# top.net
KiCad netlist of a schematic drawn in Altium Designer
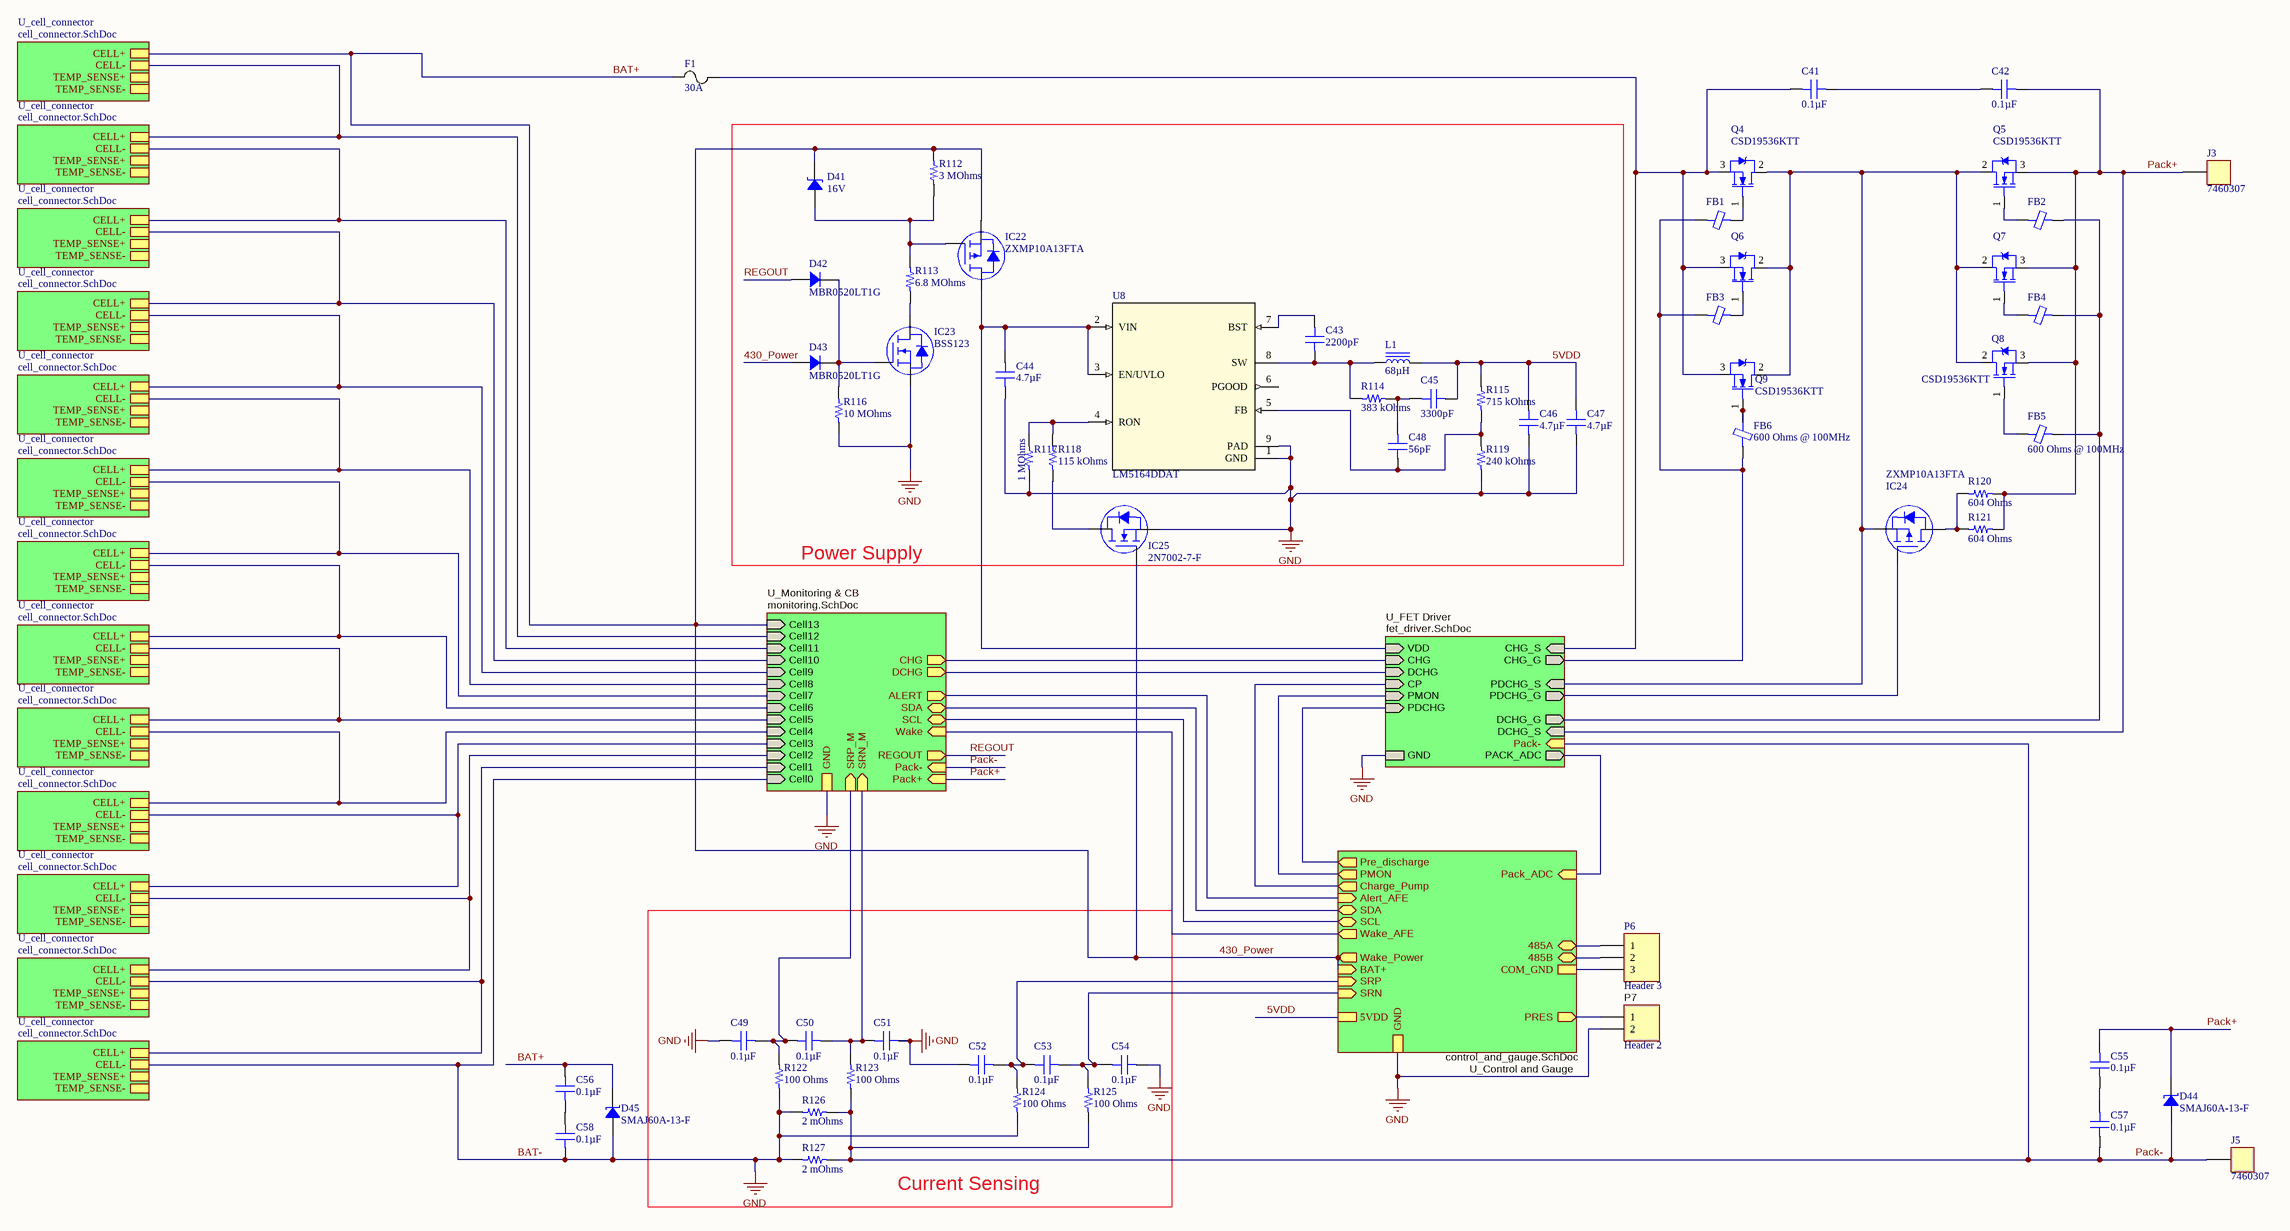
[diagram p0: top.SchDoc]

(export (version "E")
  (design (tool "Eeschema 10.0.6"))
  (components
    (comp (ref "C41")
      (value "0.1µF")
      (footprint "CAP 0603_1608")
      (description "CAP CER 0.1UF 100V X7R 0603")
      (fields
        (field (name "PART NUMBER") "GCJ188R72A104KA01D")
        (field (name "MANUFACTURER") "Murata Electronics")
      )
      (libsource (lib "Celestial Altium Library - altium_library") (part "Capacitor"))
    )
    (comp (ref "C42")
      (value "0.1µF")
      (footprint "CAP 0603_1608")
      (description "CAP CER 0.1UF 100V X7R 0603")
      (fields
        (field (name "PART NUMBER") "GCJ188R72A104KA01D")
        (field (name "MANUFACTURER") "Murata Electronics")
      )
      (libsource (lib "Celestial Altium Library - altium_library") (part "Capacitor"))
    )
    (comp (ref "C43")
      (value "2200pF")
      (footprint "CAP 0603_1608")
      (description "CAP CER 2200PF 50V C0G 0603")
      (fields
        (field (name "PART NUMBER") "C1608C0G1H222J080AA")
        (field (name "MANUFACTURER") "TDK Corporation")
      )
      (libsource (lib "Celestial Altium Library - altium_library") (part "Capacitor"))
    )
    (comp (ref "C44")
      (value "4.7µF")
      (footprint "CAP 1210_3225 - 2.2MM")
      (description "CAP CER 4.7UF 100V X7S 1210")
      (fields
        (field (name "PART NUMBER") "C3225X7S2A475K200AB")
        (field (name "MANUFACTURER") "TDK Corporation")
      )
      (libsource (lib "Celestial Altium Library - altium_library") (part "Capacitor"))
    )
    (comp (ref "C45")
      (value "3300pF")
      (footprint "CAP 0603_1608")
      (description "CAP CER 3300PF 50V X7R 0603")
      (fields
        (field (name "PART NUMBER") "CGA3E2X7R1H332K080AA")
        (field (name "MANUFACTURER") "TDK Corporation")
      )
      (libsource (lib "Celestial Altium Library - altium_library") (part "Capacitor"))
    )
    (comp (ref "C46")
      (value "4.7µF")
      (footprint "CAP 0805_2012")
      (description "CAP CER 4.7UF 16V X7R 0805")
      (fields (field (name "PART NUMBER") "CC0805KKX7R7BB475") (field (name "MANUFACTURER") "Yageo"))
      (libsource (lib "Celestial Altium Library - altium_library") (part "Capacitor"))
    )
    (comp (ref "C47")
      (value "4.7µF")
      (footprint "CAP 0805_2012")
      (description "CAP CER 4.7UF 16V X7R 0805")
      (fields (field (name "PART NUMBER") "CC0805KKX7R7BB475") (field (name "MANUFACTURER") "Yageo"))
      (libsource (lib "Celestial Altium Library - altium_library") (part "Capacitor"))
    )
    (comp (ref "C48")
      (value "56pF")
      (footprint "CAP 0603_1608")
      (description "CAP CER 56PF 50V C0G 0603")
      (fields
        (field (name "PART NUMBER") "CGA3E2C0G1H560J080AA")
        (field (name "MANUFACTURER") "TDK Corporation")
      )
      (libsource (lib "Celestial Altium Library - altium_library") (part "Capacitor"))
    )
    (comp (ref "C49")
      (value "0.1µF")
      (footprint "CAP 0603_1608")
      (description "CAP CER 0.1UF 50V X7R 0603")
      (fields
        (field (name "PART NUMBER") "GCJ188R71H104KA12D")
        (field (name "MANUFACTURER") "Murata Electronics")
      )
      (libsource (lib "Celestial Altium Library - altium_library") (part "Capacitor"))
    )
    (comp (ref "C50")
      (value "0.1µF")
      (footprint "CAP 0603_1608")
      (description "CAP CER 0.1UF 50V X7R 0603")
      (fields
        (field (name "PART NUMBER") "GCJ188R71H104KA12D")
        (field (name "MANUFACTURER") "Murata Electronics")
      )
      (libsource (lib "Celestial Altium Library - altium_library") (part "Capacitor"))
    )
    (comp (ref "C51")
      (value "0.1µF")
      (footprint "CAP 0603_1608")
      (description "CAP CER 0.1UF 50V X7R 0603")
      (fields
        (field (name "PART NUMBER") "GCJ188R71H104KA12D")
        (field (name "MANUFACTURER") "Murata Electronics")
      )
      (libsource (lib "Celestial Altium Library - altium_library") (part "Capacitor"))
    )
    (comp (ref "C52")
      (value "0.1µF")
      (footprint "CAP 0603_1608")
      (description "CAP CER 0.1UF 50V X7R 0603")
      (fields
        (field (name "PART NUMBER") "GCJ188R71H104KA12D")
        (field (name "MANUFACTURER") "Murata Electronics")
      )
      (libsource (lib "Celestial Altium Library - altium_library") (part "Capacitor"))
    )
    (comp (ref "C53")
      (value "0.1µF")
      (footprint "CAP 0603_1608")
      (description "CAP CER 0.1UF 50V X7R 0603")
      (fields
        (field (name "PART NUMBER") "GCJ188R71H104KA12D")
        (field (name "MANUFACTURER") "Murata Electronics")
      )
      (libsource (lib "Celestial Altium Library - altium_library") (part "Capacitor"))
    )
    (comp (ref "C54")
      (value "0.1µF")
      (footprint "CAP 0603_1608")
      (description "CAP CER 0.1UF 50V X7R 0603")
      (fields
        (field (name "PART NUMBER") "GCJ188R71H104KA12D")
        (field (name "MANUFACTURER") "Murata Electronics")
      )
      (libsource (lib "Celestial Altium Library - altium_library") (part "Capacitor"))
    )
    (comp (ref "C55")
      (value "0.1µF")
      (footprint "CAP 0603_1608")
      (description "CAP CER 0.1UF 100V X7R 0603")
      (fields
        (field (name "PART NUMBER") "GCJ188R72A104KA01D")
        (field (name "MANUFACTURER") "Murata Electronics")
      )
      (libsource (lib "Celestial Altium Library - altium_library") (part "Capacitor"))
    )
    (comp (ref "C56")
      (value "0.1µF")
      (footprint "CAP 0603_1608")
      (description "CAP CER 0.1UF 100V X7R 0603")
      (fields
        (field (name "PART NUMBER") "GCJ188R72A104KA01D")
        (field (name "MANUFACTURER") "Murata Electronics")
      )
      (libsource (lib "Celestial Altium Library - altium_library") (part "Capacitor"))
    )
    (comp (ref "C57")
      (value "0.1µF")
      (footprint "CAP 0603_1608")
      (description "CAP CER 0.1UF 100V X7R 0603")
      (fields
        (field (name "PART NUMBER") "GCJ188R72A104KA01D")
        (field (name "MANUFACTURER") "Murata Electronics")
      )
      (libsource (lib "Celestial Altium Library - altium_library") (part "Capacitor"))
    )
    (comp (ref "C58")
      (value "0.1µF")
      (footprint "CAP 0603_1608")
      (description "CAP CER 0.1UF 100V X7R 0603")
      (fields
        (field (name "PART NUMBER") "GCJ188R72A104KA01D")
        (field (name "MANUFACTURER") "Murata Electronics")
      )
      (libsource (lib "Celestial Altium Library - altium_library") (part "Capacitor"))
    )
    (comp (ref "D41")
      (value "MMSZ5246B-7-F")
      (footprint "SOD-123")
      (description "DIODE ZENER 16V 500MW SOD123")
      (fields
        (field (name "MANUFACTURER") "Diodes Incorporated")
        (field (name "TOLERANCE") "±5%")
        (field (name "VOLTAGE - ZENER (NOM) (VZ)") "16V")
      )
      (libsource (lib "Celestial Altium Library - altium_library") (part "Diode Zener"))
    )
    (comp (ref "D42")
      (value "MBR0520LT1G")
      (footprint "SOD-123")
      (description "DIODE SCHOTTKY 20V 500MA SOD123")
      (fields (field (name "MANUFACTURER") "ON Semiconductor"))
      (libsource (lib "Celestial Altium Library - altium_library") (part "Diode"))
    )
    (comp (ref "D43")
      (value "MBR0520LT1G")
      (footprint "SOD-123")
      (description "DIODE SCHOTTKY 20V 500MA SOD123")
      (fields (field (name "MANUFACTURER") "ON Semiconductor"))
      (libsource (lib "Celestial Altium Library - altium_library") (part "Diode"))
    )
    (comp (ref "D44")
      (value "SMAJ60A-13-F")
      (footprint "DO214AC SMA")
      (description "TVS DIODE 60V 96.8V SMA")
      (fields (field (name "MANUFACTURER") "Diodes Incorporated"))
      (libsource (lib "Celestial Altium Library - altium_library") (part "DIODE TVS UNI"))
    )
    (comp (ref "D45")
      (value "SMAJ60A-13-F")
      (footprint "DO214AC SMA")
      (description "TVS DIODE 60V 96.8V SMA")
      (fields (field (name "MANUFACTURER") "Diodes Incorporated"))
      (libsource (lib "Celestial Altium Library - altium_library") (part "DIODE TVS UNI"))
    )
    (comp (ref "F1")
      (value "0456030.ER")
      (footprint "FUS_LITTELFUSE_0456_30A_LTF")
      (description "AC DC Fuse Board Mount (Cartridge Style Excluded) Surface Mount 2-SMD, Square End Block")
      (fields
        (field (name "MANUFACTURER") "Littelfuse")
        (field (name "FUSE CURRENT") "30A")
        (field (name "COPYRIGHT") "Copyright (C) 2018 Accelerated Designs. All rights reserved")
      )
      (libsource (lib "bms") (part "0456030.ER"))
    )
    (comp (ref "FB1")
      (value "600 Ohms @ 100MHz")
      (footprint "FER 0603_1608")
      (description "FERRITE BEAD 600 OHM 0603 1LN")
      (fields (field (name "PART NUMBER") "74279265") (field (name "MANUFACTURER") "Würth Elektronik"))
      (libsource (lib "Celestial Altium Library - altium_library") (part "Ferrite Chip"))
    )
    (comp (ref "FB2")
      (value "600 Ohms @ 100MHz")
      (footprint "FER 0603_1608")
      (description "FERRITE BEAD 600 OHM 0603 1LN")
      (fields (field (name "PART NUMBER") "74279265") (field (name "MANUFACTURER") "Würth Elektronik"))
      (libsource (lib "Celestial Altium Library - altium_library") (part "Ferrite Chip"))
    )
    (comp (ref "FB3")
      (value "600 Ohms @ 100MHz")
      (footprint "FER 0603_1608")
      (description "FERRITE BEAD 600 OHM 0603 1LN")
      (fields (field (name "PART NUMBER") "74279265") (field (name "MANUFACTURER") "Würth Elektronik"))
      (libsource (lib "Celestial Altium Library - altium_library") (part "Ferrite Chip"))
    )
    (comp (ref "FB4")
      (value "600 Ohms @ 100MHz")
      (footprint "FER 0603_1608")
      (description "FERRITE BEAD 600 OHM 0603 1LN")
      (fields (field (name "PART NUMBER") "74279265") (field (name "MANUFACTURER") "Würth Elektronik"))
      (libsource (lib "Celestial Altium Library - altium_library") (part "Ferrite Chip"))
    )
    (comp (ref "FB5")
      (value "600 Ohms @ 100MHz")
      (footprint "FER 0603_1608")
      (description "FERRITE BEAD 600 OHM 0603 1LN")
      (fields (field (name "PART NUMBER") "74279265") (field (name "MANUFACTURER") "Würth Elektronik"))
      (libsource (lib "Celestial Altium Library - altium_library") (part "Ferrite Chip"))
    )
    (comp (ref "FB6")
      (value "600 Ohms @ 100MHz")
      (footprint "FER 0603_1608")
      (description "FERRITE BEAD 600 OHM 0603 1LN")
      (fields (field (name "PART NUMBER") "74279265") (field (name "MANUFACTURER") "Würth Elektronik"))
      (libsource (lib "Celestial Altium Library - altium_library") (part "Ferrite Chip"))
    )
    (comp (ref "IC22")
      (value "ZXMP10A13FTA")
      (footprint "DIODES SOT-23-3")
      (description "MOSFET P-CH 100V 0.6A SOT23-3")
      (fields (field (name "MANUFACTURER") "Diodes Incorporated"))
      (libsource (lib "Celestial Altium Library - altium_library") (part "DIODES MOSFET P-CH SOT-23-3"))
    )
    (comp (ref "IC23")
      (value "BSS123")
      (footprint "ON SEMI SOT-23-3")
      (description "MOSFET N-CH 100V 170MA SOT-23")
      (fields (field (name "MANUFACTURER") "ON Semiconductor"))
      (libsource (lib "Celestial Altium Library - altium_library") (part "ON SEMI MOSFET N-CH SOT-23-3"))
    )
    (comp (ref "IC24")
      (value "ZXMP10A13FTA")
      (footprint "DIODES SOT-23-3")
      (description "MOSFET P-CH 100V 0.6A SOT23-3")
      (fields (field (name "MANUFACTURER") "Diodes Incorporated"))
      (libsource (lib "Celestial Altium Library - altium_library") (part "DIODES MOSFET P-CH SOT-23-3"))
    )
    (comp (ref "IC25")
      (value "2N7002-7-F")
      (footprint "DIODES SOT-23-3")
      (description "MOSFET N-CH 60V 115MA SOT23-3")
      (fields (field (name "MANUFACTURER") "Diodes Incorporated"))
      (libsource (lib "Celestial Altium Library - altium_library") (part "DIODES INC MOSFET N-CH SOT-23-3"))
    )
    (comp (ref "J3")
      (value "7460307")
      (footprint "7460307")
      (description "TERM REDCUBE M4 8PIN PCB 160A Current")
      (fields
        (field (name "MOUSER PART NUMBER") "710-7460307")
        (field (name "MANUFACTURER") "Wurth Electronics")
      )
      (libsource (lib "bms") (part "7460307"))
    )
    (comp (ref "J5")
      (value "7460307")
      (footprint "7460307")
      (description "TERM REDCUBE M4 8PIN PCB 160A Current")
      (fields
        (field (name "MOUSER PART NUMBER") "710-7460307")
        (field (name "MANUFACTURER") "Wurth Electronics")
      )
      (libsource (lib "bms") (part "7460307"))
    )
    (comp (ref "L1")
      (value "68µH")
      (footprint "TDK SLF10145")
      (description "FIXED IND 68UH 1.3A 168 MOHM SMD")
      (fields
        (field (name "PART NUMBER") "SLF10145T-680M1R2-PF")
        (field (name "MANUFACTURER") "TDK Corporation")
      )
      (libsource (lib "Celestial Altium Library - altium_library") (part "Inductor"))
    )
    (comp (ref "P6")
      (value "Header 3")
      (footprint "HDR1X3")
      (description "Header, 3-Pin")
      (fields (field (name "PUBLISHER") "Altium Limited"))
      (libsource (lib "Miscellaneous Connectors") (part "Header 3"))
    )
    (comp (ref "P7")
      (value "Header 2")
      (footprint "HDR1X2")
      (description "Header, 2-Pin")
      (fields (field (name "PUBLISHER") "Altium Limited"))
      (libsource (lib "Miscellaneous Connectors") (part "Header 2"))
    )
    (comp (ref "Q4")
      (value "CSD19536KTT")
      (footprint "DDPAK")
      (fields (field (name "MANUFACTURER") "Texas Instruments"))
      (libsource (lib "bms") (part "CSD19536KTT"))
    )
    (comp (ref "Q5")
      (value "CSD19536KTT")
      (footprint "DDPAK")
      (fields (field (name "MANUFACTURER") "Texas Instruments"))
      (libsource (lib "bms") (part "CSD19536KTT"))
    )
    (comp (ref "Q6")
      (value "CSD19536KTT")
      (footprint "DDPAK")
      (fields (field (name "MANUFACTURER") "Texas Instruments"))
      (libsource (lib "bms") (part "CSD19536KTT"))
    )
    (comp (ref "Q7")
      (value "CSD19536KTT")
      (footprint "DDPAK")
      (fields (field (name "MANUFACTURER") "Texas Instruments"))
      (libsource (lib "bms") (part "CSD19536KTT"))
    )
    (comp (ref "Q8")
      (value "CSD19536KTT")
      (footprint "DDPAK")
      (fields (field (name "MANUFACTURER") "Texas Instruments"))
      (libsource (lib "bms") (part "CSD19536KTT"))
    )
    (comp (ref "Q9")
      (value "CSD19536KTT")
      (footprint "DDPAK")
      (fields (field (name "MANUFACTURER") "Texas Instruments"))
      (libsource (lib "bms") (part "CSD19536KTT"))
    )
    (comp (ref "R112")
      (value "3 MOhms")
      (footprint "RES 0603_1608")
      (description "RES SMD 3M OHM 1% 1/10W 0603")
      (fields (field (name "PART NUMBER") "CRCW06033M00FKEA") (field (name "MANUFACTURER") "Vishay Dale"))
      (libsource (lib "Celestial Altium Library - altium_library") (part "Resistor"))
    )
    (comp (ref "R113")
      (value "6.8 MOhms")
      (footprint "RES 0603_1608")
      (description "RES SMD 6.8M OHM 1% 1/10W 0603")
      (fields (field (name "PART NUMBER") "CRCW06036M80FKEA") (field (name "MANUFACTURER") "Vishay Dale"))
      (libsource (lib "Celestial Altium Library - altium_library") (part "Resistor"))
    )
    (comp (ref "R114")
      (value "383 kOhms")
      (footprint "RES 0603_1608")
      (description "RES SMD 383K OHM 1% 1/10W 0603")
      (fields (field (name "PART NUMBER") "CRCW0603383KFKEA") (field (name "MANUFACTURER") "Vishay Dale"))
      (libsource (lib "Celestial Altium Library - altium_library") (part "Resistor"))
    )
    (comp (ref "R115")
      (value "715 kOhms")
      (footprint "RES 0603_1608")
      (description "RES SMD 715K OHM 1% 1/10W 0603")
      (fields (field (name "PART NUMBER") "CRCW0603715KFKEA") (field (name "MANUFACTURER") "Vishay Dale"))
      (libsource (lib "Celestial Altium Library - altium_library") (part "Resistor"))
    )
    (comp (ref "R116")
      (value "10 MOhms")
      (footprint "RES 0603_1608")
      (description "RES SMD 10M OHM 1% 1/10W 0603")
      (fields (field (name "PART NUMBER") "CRCW060310M0FKEA") (field (name "MANUFACTURER") "Vishay Dale"))
      (libsource (lib "Celestial Altium Library - altium_library") (part "Resistor"))
    )
    (comp (ref "R117")
      (value "1 MOhms")
      (footprint "RES 0603_1608")
      (description "RES SMD 1M OHM 1% 1/10W 0603")
      (fields (field (name "PART NUMBER") "CRCW06031M00FKEA") (field (name "MANUFACTURER") "Vishay Dale"))
      (libsource (lib "Celestial Altium Library - altium_library") (part "Resistor"))
    )
    (comp (ref "R118")
      (value "115 kOhms")
      (footprint "RES 0603_1608")
      (description "RES SMD 115K OHM 1% 1/10W 0603")
      (fields (field (name "PART NUMBER") "CRCW0603115KFKEA") (field (name "MANUFACTURER") "Vishay Dale"))
      (libsource (lib "Celestial Altium Library - altium_library") (part "Resistor"))
    )
    (comp (ref "R119")
      (value "240 kOhms")
      (footprint "RES 0603_1608")
      (description "RES SMD 240K OHM 1% 1/10W 0603")
      (fields (field (name "PART NUMBER") "CRCW0603240KFKEA") (field (name "MANUFACTURER") "Vishay Dale"))
      (libsource (lib "Celestial Altium Library - altium_library") (part "Resistor"))
    )
    (comp (ref "R120")
      (value "604 Ohms")
      (footprint "RES 2512_6432")
      (description "RES SMD 604 OHM 1% 1W 2512")
      (fields (field (name "PART NUMBER") "CRCW2512604RFKEG") (field (name "MANUFACTURER") "Vishay Dale"))
      (libsource (lib "Celestial Altium Library - altium_library") (part "Resistor"))
    )
    (comp (ref "R121")
      (value "604 Ohms")
      (footprint "RES 2512_6432")
      (description "RES SMD 604 OHM 1% 1W 2512")
      (fields (field (name "PART NUMBER") "CRCW2512604RFKEG") (field (name "MANUFACTURER") "Vishay Dale"))
      (libsource (lib "Celestial Altium Library - altium_library") (part "Resistor"))
    )
    (comp (ref "R122")
      (value "100 Ohms")
      (footprint "RES 0603_1608")
      (description "RES SMD 100 OHM 1% 1/10W 0603")
      (fields (field (name "PART NUMBER") "CRCW0603100RFKTA") (field (name "MANUFACTURER") "Vishay Dale"))
      (libsource (lib "Celestial Altium Library - altium_library") (part "Resistor"))
    )
    (comp (ref "R123")
      (value "100 Ohms")
      (footprint "RES 0603_1608")
      (description "RES SMD 100 OHM 1% 1/10W 0603")
      (fields (field (name "PART NUMBER") "CRCW0603100RFKTA") (field (name "MANUFACTURER") "Vishay Dale"))
      (libsource (lib "Celestial Altium Library - altium_library") (part "Resistor"))
    )
    (comp (ref "R124")
      (value "100 Ohms")
      (footprint "RES 0603_1608")
      (description "RES SMD 100 OHM 1% 1/10W 0603")
      (fields (field (name "PART NUMBER") "CRCW0603100RFKTA") (field (name "MANUFACTURER") "Vishay Dale"))
      (libsource (lib "Celestial Altium Library - altium_library") (part "Resistor"))
    )
    (comp (ref "R125")
      (value "100 Ohms")
      (footprint "RES 0603_1608")
      (description "RES SMD 100 OHM 1% 1/10W 0603")
      (fields (field (name "PART NUMBER") "CRCW0603100RFKTA") (field (name "MANUFACTURER") "Vishay Dale"))
      (libsource (lib "Celestial Altium Library - altium_library") (part "Resistor"))
    )
    (comp (ref "R126")
      (value "2 mOhms")
      (footprint "STACKPOLE CSR2512")
      (description "RES 0.002 OHM 5% 2W 2512")
      (fields
        (field (name "PART NUMBER") "PMR100HZPJV2L0")
        (field (name "MANUFACTURER") "Rohm Semiconductor")
      )
      (libsource (lib "Celestial Altium Library - altium_library") (part "Resistor"))
    )
    (comp (ref "R127")
      (value "2 mOhms")
      (footprint "STACKPOLE CSR2512")
      (description "RES 0.002 OHM 5% 2W 2512")
      (fields
        (field (name "PART NUMBER") "PMR100HZPJV2L0")
        (field (name "MANUFACTURER") "Rohm Semiconductor")
      )
      (libsource (lib "Celestial Altium Library - altium_library") (part "Resistor"))
    )
    (comp (ref "U8")
      (value "LM5164DDAT")
      (footprint "PowerSOIC_8")
      (fields
        (field (name "MANUFACTURER") "Texas Instruments")
        (field (name "COPYRIGHT") "Copyright (C) 2018 Accelerated Designs. All rights reserved")
      )
      (libsource (lib "bms") (part "LM5164DDAT"))
    )
  )
  (nets
    (net (code "1") (name "/5VDD") (class "Default")
      (node (ref "C45") (pin "2") (pinfunction "2_2") (pintype "passive"))
      (node (ref "C46") (pin "2") (pinfunction "2_2") (pintype "passive"))
      (node (ref "C47") (pin "2") (pinfunction "2_2") (pintype "passive"))
      (node (ref "L1") (pin "2") (pinfunction "2_2") (pintype "passive"))
      (node (ref "R115") (pin "2") (pinfunction "2_2") (pintype "passive"))
    )
    (net (code "2") (name "/430_Power") (class "Default")
      (node (ref "C56") (pin "2") (pinfunction "2_2") (pintype "passive"))
      (node (ref "D41") (pin "2") (pinfunction "2_2") (pintype "passive"))
      (node (ref "D43") (pin "1") (pinfunction "1_1") (pintype "passive"))
      (node (ref "D45") (pin "2") (pinfunction "2_2") (pintype "passive"))
      (node (ref "F1") (pin "1") (pinfunction "1_1") (pintype "passive"))
      (node (ref "IC22") (pin "2") (pinfunction "S_2") (pintype "passive"))
      (node (ref "IC25") (pin "1") (pinfunction "G_1") (pintype "passive"))
      (node (ref "R112") (pin "2") (pinfunction "2_2") (pintype "passive"))
    )
    (net (code "3") (name "/485A") (class "Default")
      (node (ref "P6") (pin "1") (pinfunction "1_1") (pintype "passive"))
    )
    (net (code "4") (name "/485B") (class "Default")
      (node (ref "P6") (pin "2") (pinfunction "2_2") (pintype "passive"))
    )
    (net (code "19") (name "/CHG_G") (class "Default")
      (node (ref "FB1") (pin "2") (pinfunction "2_2") (pintype "passive"))
      (node (ref "FB3") (pin "2") (pinfunction "2_2") (pintype "passive"))
      (node (ref "FB6") (pin "1") (pinfunction "1_1") (pintype "passive"))
    )
    (net (code "20") (name "/CHG_S") (class "Default")
      (node (ref "C41") (pin "2") (pinfunction "2_2") (pintype "passive"))
      (node (ref "F1") (pin "2") (pinfunction "2_2") (pintype "passive"))
      (node (ref "Q4") (pin "3") (pinfunction "S_3") (pintype "passive"))
      (node (ref "Q6") (pin "3") (pinfunction "S_3") (pintype "passive"))
      (node (ref "Q9") (pin "3") (pinfunction "S_3") (pintype "passive"))
    )
    (net (code "21") (name "/COM_GND") (class "Default")
      (node (ref "P6") (pin "3") (pinfunction "3_3") (pintype "passive"))
    )
    (net (code "24") (name "/DCHG_G") (class "Default")
      (node (ref "FB2") (pin "1") (pinfunction "1_1") (pintype "passive"))
      (node (ref "FB4") (pin "1") (pinfunction "1_1") (pintype "passive"))
      (node (ref "FB5") (pin "1") (pinfunction "1_1") (pintype "passive"))
    )
    (net (code "26") (name "/PDCHG_G") (class "Default")
      (node (ref "IC24") (pin "1") (pinfunction "G_1") (pintype "passive"))
    )
    (net (code "27") (name "/PDCHG_S") (class "Default")
      (node (ref "IC24") (pin "2") (pinfunction "S_2") (pintype "passive"))
      (node (ref "Q4") (pin "2") (pinfunction "D_2") (pintype "passive"))
      (node (ref "Q5") (pin "2") (pinfunction "D_2") (pintype "passive"))
      (node (ref "Q6") (pin "2") (pinfunction "D_2") (pintype "passive"))
      (node (ref "Q7") (pin "2") (pinfunction "D_2") (pintype "passive"))
      (node (ref "Q8") (pin "2") (pinfunction "D_2") (pintype "passive"))
      (node (ref "Q9") (pin "2") (pinfunction "D_2") (pintype "passive"))
    )
    (net (code "29") (name "/PRES") (class "Default")
      (node (ref "P7") (pin "1") (pinfunction "1_1") (pintype "passive"))
    )
    (net (code "30") (name "/Pack+") (class "Default")
      (node (ref "C42") (pin "1") (pinfunction "1_1") (pintype "passive"))
      (node (ref "C55") (pin "2") (pinfunction "2_2") (pintype "passive"))
      (node (ref "D44") (pin "2") (pinfunction "2_2") (pintype "passive"))
      (node (ref "J3") (pin "1") (pinfunction "1_1") (pintype "power_in"))
      (node (ref "Q5") (pin "3") (pinfunction "S_3") (pintype "passive"))
      (node (ref "Q7") (pin "3") (pinfunction "S_3") (pintype "passive"))
      (node (ref "Q8") (pin "3") (pinfunction "S_3") (pintype "passive"))
      (node (ref "R120") (pin "2") (pinfunction "2_2") (pintype "passive"))
      (node (ref "R121") (pin "2") (pinfunction "2_2") (pintype "passive"))
    )
    (net (code "31") (name "/Pack-") (class "Default")
      (node (ref "C57") (pin "1") (pinfunction "1_1") (pintype "passive"))
      (node (ref "D44") (pin "1") (pinfunction "1_1") (pintype "passive"))
      (node (ref "J5") (pin "1") (pinfunction "1_1") (pintype "power_in"))
      (node (ref "R123") (pin "2") (pinfunction "2_2") (pintype "passive"))
      (node (ref "R125") (pin "2") (pinfunction "2_2") (pintype "passive"))
      (node (ref "R126") (pin "2") (pinfunction "2_2") (pintype "passive"))
      (node (ref "R127") (pin "2") (pinfunction "2_2") (pintype "passive"))
    )
    (net (code "33") (name "/REGOUT") (class "Default")
      (node (ref "D42") (pin "1") (pinfunction "1_1") (pintype "passive"))
    )
    (net (code "36") (name "/SRN") (class "Default")
      (node (ref "C53") (pin "2") (pinfunction "2_2") (pintype "passive"))
      (node (ref "C54") (pin "1") (pinfunction "1_1") (pintype "passive"))
      (node (ref "R125") (pin "1") (pinfunction "1_1") (pintype "passive"))
    )
    (net (code "37") (name "/SRN_M") (class "Default")
      (node (ref "C50") (pin "2") (pinfunction "2_2") (pintype "passive"))
      (node (ref "C51") (pin "1") (pinfunction "1_1") (pintype "passive"))
      (node (ref "R123") (pin "1") (pinfunction "1_1") (pintype "passive"))
    )
    (net (code "38") (name "/SRP") (class "Default")
      (node (ref "C52") (pin "2") (pinfunction "2_2") (pintype "passive"))
      (node (ref "C53") (pin "1") (pinfunction "1_1") (pintype "passive"))
      (node (ref "R124") (pin "1") (pinfunction "1_1") (pintype "passive"))
    )
    (net (code "39") (name "/SRP_M") (class "Default")
      (node (ref "C49") (pin "2") (pinfunction "2_2") (pintype "passive"))
      (node (ref "C50") (pin "1") (pinfunction "1_1") (pintype "passive"))
      (node (ref "R122") (pin "1") (pinfunction "1_1") (pintype "passive"))
    )
    (net (code "66") (name "/VDD") (class "Default")
      (node (ref "C44") (pin "2") (pinfunction "2_2") (pintype "passive"))
      (node (ref "IC22") (pin "3") (pinfunction "D_3") (pintype "passive"))
      (node (ref "U8") (pin "2") (pinfunction "VIN_2") (pintype "input"))
      (node (ref "U8") (pin "3") (pinfunction "EN/UVLO_3") (pintype "input"))
    )
    (net (code "68") (name "GND") (class "Default")
      (node (ref "C44") (pin "1") (pinfunction "1_1") (pintype "passive"))
      (node (ref "C46") (pin "1") (pinfunction "1_1") (pintype "passive"))
      (node (ref "C47") (pin "1") (pinfunction "1_1") (pintype "passive"))
      (node (ref "C49") (pin "1") (pinfunction "1_1") (pintype "passive"))
      (node (ref "C51") (pin "2") (pinfunction "2_2") (pintype "passive"))
      (node (ref "C52") (pin "1") (pinfunction "1_1") (pintype "passive"))
      (node (ref "C54") (pin "2") (pinfunction "2_2") (pintype "passive"))
      (node (ref "C58") (pin "1") (pinfunction "1_1") (pintype "passive"))
      (node (ref "D45") (pin "1") (pinfunction "1_1") (pintype "passive"))
      (node (ref "IC23") (pin "2") (pinfunction "S_2") (pintype "passive"))
      (node (ref "IC25") (pin "2") (pinfunction "S_2") (pintype "passive"))
      (node (ref "P7") (pin "2") (pinfunction "2_2") (pintype "passive"))
      (node (ref "R116") (pin "1") (pinfunction "1_1") (pintype "passive"))
      (node (ref "R117") (pin "2") (pinfunction "2_2") (pintype "passive"))
      (node (ref "R119") (pin "1") (pinfunction "1_1") (pintype "passive"))
      (node (ref "R122") (pin "2") (pinfunction "2_2") (pintype "passive"))
      (node (ref "R124") (pin "2") (pinfunction "2_2") (pintype "passive"))
      (node (ref "R126") (pin "1") (pinfunction "1_1") (pintype "passive"))
      (node (ref "R127") (pin "1") (pinfunction "1_1") (pintype "passive"))
      (node (ref "U8") (pin "1") (pinfunction "GND_1") (pintype "power_in"))
      (node (ref "U8") (pin "9") (pinfunction "PAD_9") (pintype "power_in"))
    )
    (net (code "69") (name "Net-(C41-Pad1)") (class "Default")
      (node (ref "C41") (pin "1") (pinfunction "1_1") (pintype "passive"))
      (node (ref "C42") (pin "2") (pinfunction "2_2") (pintype "passive"))
    )
    (net (code "70") (name "Net-(C45-Pad1)") (class "Default")
      (node (ref "C45") (pin "1") (pinfunction "1_1") (pintype "passive"))
      (node (ref "C48") (pin "2") (pinfunction "2_2") (pintype "passive"))
      (node (ref "R114") (pin "2") (pinfunction "2_2") (pintype "passive"))
    )
    (net (code "71") (name "Net-(C55-Pad1)") (class "Default")
      (node (ref "C55") (pin "1") (pinfunction "1_1") (pintype "passive"))
      (node (ref "C57") (pin "2") (pinfunction "2_2") (pintype "passive"))
    )
    (net (code "72") (name "Net-(C56-Pad1)") (class "Default")
      (node (ref "C56") (pin "1") (pinfunction "1_1") (pintype "passive"))
      (node (ref "C58") (pin "2") (pinfunction "2_2") (pintype "passive"))
    )
    (net (code "73") (name "Net-(IC22-G)") (class "Default")
      (node (ref "D41") (pin "1") (pinfunction "1_1") (pintype "passive"))
      (node (ref "IC22") (pin "1") (pinfunction "G_1") (pintype "passive"))
      (node (ref "R112") (pin "1") (pinfunction "1_1") (pintype "passive"))
      (node (ref "R113") (pin "2") (pinfunction "2_2") (pintype "passive"))
    )
    (net (code "74") (name "Net-(IC23-D)") (class "Default")
      (node (ref "IC23") (pin "3") (pinfunction "D_3") (pintype "passive"))
      (node (ref "R113") (pin "1") (pinfunction "1_1") (pintype "passive"))
    )
    (net (code "75") (name "Net-(IC23-G)") (class "Default")
      (node (ref "D42") (pin "2") (pinfunction "2_2") (pintype "passive"))
      (node (ref "D43") (pin "2") (pinfunction "2_2") (pintype "passive"))
      (node (ref "IC23") (pin "1") (pinfunction "G_1") (pintype "passive"))
      (node (ref "R116") (pin "2") (pinfunction "2_2") (pintype "passive"))
    )
    (net (code "76") (name "Net-(IC24-D)") (class "Default")
      (node (ref "IC24") (pin "3") (pinfunction "D_3") (pintype "passive"))
      (node (ref "R120") (pin "1") (pinfunction "1_1") (pintype "passive"))
      (node (ref "R121") (pin "1") (pinfunction "1_1") (pintype "passive"))
    )
    (net (code "77") (name "Net-(IC25-D)") (class "Default")
      (node (ref "IC25") (pin "3") (pinfunction "D_3") (pintype "passive"))
      (node (ref "R118") (pin "1") (pinfunction "1_1") (pintype "passive"))
    )
    (net (code "78") (name "Net-(Q4-G)") (class "Default")
      (node (ref "FB1") (pin "1") (pinfunction "1_1") (pintype "passive"))
      (node (ref "Q4") (pin "1") (pinfunction "G_1") (pintype "passive"))
    )
    (net (code "79") (name "Net-(Q5-G)") (class "Default")
      (node (ref "FB2") (pin "2") (pinfunction "2_2") (pintype "passive"))
      (node (ref "Q5") (pin "1") (pinfunction "G_1") (pintype "passive"))
    )
    (net (code "80") (name "Net-(Q6-G)") (class "Default")
      (node (ref "FB3") (pin "1") (pinfunction "1_1") (pintype "passive"))
      (node (ref "Q6") (pin "1") (pinfunction "G_1") (pintype "passive"))
    )
    (net (code "81") (name "Net-(Q7-G)") (class "Default")
      (node (ref "FB4") (pin "2") (pinfunction "2_2") (pintype "passive"))
      (node (ref "Q7") (pin "1") (pinfunction "G_1") (pintype "passive"))
    )
    (net (code "82") (name "Net-(Q8-G)") (class "Default")
      (node (ref "FB5") (pin "2") (pinfunction "2_2") (pintype "passive"))
      (node (ref "Q8") (pin "1") (pinfunction "G_1") (pintype "passive"))
    )
    (net (code "83") (name "Net-(Q9-G)") (class "Default")
      (node (ref "FB6") (pin "2") (pinfunction "2_2") (pintype "passive"))
      (node (ref "Q9") (pin "1") (pinfunction "G_1") (pintype "passive"))
    )
    (net (code "84") (name "Net-(U8-BST)") (class "Default")
      (node (ref "C43") (pin "2") (pinfunction "2_2") (pintype "passive"))
      (node (ref "U8") (pin "7") (pinfunction "BST_7") (pintype "input"))
    )
    (net (code "85") (name "Net-(U8-FB)") (class "Default")
      (node (ref "C48") (pin "1") (pinfunction "1_1") (pintype "passive"))
      (node (ref "R115") (pin "1") (pinfunction "1_1") (pintype "passive"))
      (node (ref "R119") (pin "2") (pinfunction "2_2") (pintype "passive"))
      (node (ref "U8") (pin "5") (pinfunction "FB_5") (pintype "input"))
    )
    (net (code "86") (name "Net-(U8-RON)") (class "Default")
      (node (ref "R117") (pin "1") (pinfunction "1_1") (pintype "passive"))
      (node (ref "R118") (pin "2") (pinfunction "2_2") (pintype "passive"))
      (node (ref "U8") (pin "4") (pinfunction "RON_4") (pintype "input"))
    )
    (net (code "87") (name "Net-(U8-SW)") (class "Default")
      (node (ref "C43") (pin "1") (pinfunction "1_1") (pintype "passive"))
      (node (ref "L1") (pin "1") (pinfunction "1_1") (pintype "passive"))
      (node (ref "R114") (pin "1") (pinfunction "1_1") (pintype "passive"))
      (node (ref "U8") (pin "8") (pinfunction "SW_8") (pintype "passive"))
    )
    (net (code "88") (name "unconnected-(U8-PGOOD-Pad6)") (class "Default")
      (node (ref "U8") (pin "6") (pinfunction "PGOOD_6") (pintype "output"))
    )
  )
)
